# RPi_Extension_breakout.net
KiCad netlist of a schematic drawn in EAGLE
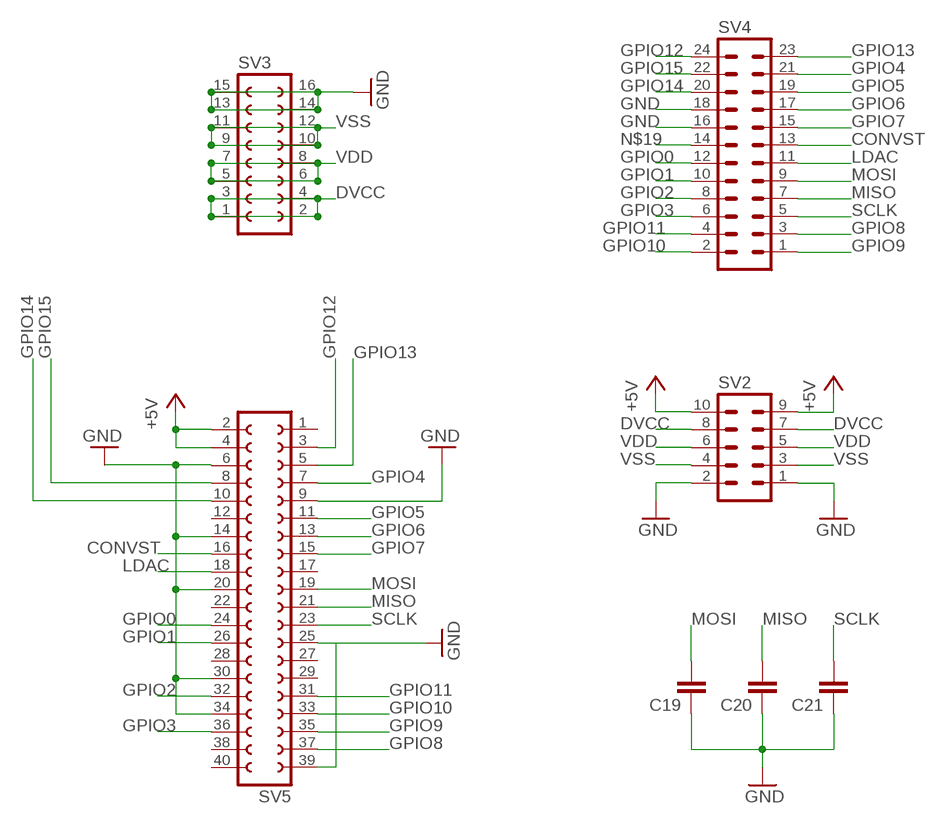
[diagram p0: schematic, sheet 1]

(export (version "E")
  (design (tool "Eeschema 10.0.6"))
  (components
    (comp (ref "C19")
      (value "C-EUC0603")
      (footprint "eagle-import:C0603")
      (libsource (lib "eagle-import") (part "C-EUC0603"))
    )
    (comp (ref "C20")
      (value "C-EUC0603")
      (footprint "eagle-import:C0603")
      (libsource (lib "eagle-import") (part "C-EUC0603"))
    )
    (comp (ref "C21")
      (value "C-EUC0603")
      (footprint "eagle-import:C0603")
      (libsource (lib "eagle-import") (part "C-EUC0603"))
    )
    (comp (ref "SV2")
      (value "MA05-2")
      (footprint "eagle-import:MA05-2")
      (libsource (lib "eagle-import") (part "MA05-2"))
    )
    (comp (ref "SV3")
      (value "FE08-2")
      (footprint "eagle-import:FE08-2")
      (libsource (lib "eagle-import") (part "FE08-2"))
    )
    (comp (ref "SV4")
      (value "MA12-2")
      (footprint "eagle-import:MA12-2")
      (libsource (lib "eagle-import") (part "MA12-2"))
    )
    (comp (ref "SV5")
      (value "FE20-2")
      (footprint "eagle-import:FE20-2")
      (libsource (lib "eagle-import") (part "FE20-2"))
    )
  )
  (nets
    (net (code "1") (name "+5V") (class "Default")
      (node (ref "SV2") (pin "10") (pinfunction "10_10") (pintype "passive"))
      (node (ref "SV2") (pin "9") (pinfunction "9_9") (pintype "passive"))
      (node (ref "SV5") (pin "2") (pinfunction "2_2") (pintype "passive"))
      (node (ref "SV5") (pin "4") (pinfunction "4_4") (pintype "passive"))
    )
    (net (code "2") (name "/CONVST") (class "Default")
      (node (ref "SV4") (pin "13") (pinfunction "13_13") (pintype "passive"))
      (node (ref "SV5") (pin "16") (pinfunction "16_16") (pintype "passive"))
    )
    (net (code "3") (name "/DVCC") (class "Default")
      (node (ref "SV2") (pin "7") (pinfunction "7_7") (pintype "passive"))
      (node (ref "SV2") (pin "8") (pinfunction "8_8") (pintype "passive"))
      (node (ref "SV3") (pin "1") (pinfunction "1_1") (pintype "passive"))
      (node (ref "SV3") (pin "2") (pinfunction "2_2") (pintype "passive"))
      (node (ref "SV3") (pin "3") (pinfunction "3_3") (pintype "passive"))
      (node (ref "SV3") (pin "4") (pinfunction "4_4") (pintype "passive"))
    )
    (net (code "4") (name "/GPIO0") (class "Default")
      (node (ref "SV4") (pin "12") (pinfunction "12_12") (pintype "passive"))
      (node (ref "SV5") (pin "24") (pinfunction "24_24") (pintype "passive"))
    )
    (net (code "5") (name "/GPIO1") (class "Default")
      (node (ref "SV4") (pin "10") (pinfunction "10_10") (pintype "passive"))
      (node (ref "SV5") (pin "26") (pinfunction "26_26") (pintype "passive"))
    )
    (net (code "6") (name "/GPIO2") (class "Default")
      (node (ref "SV4") (pin "8") (pinfunction "8_8") (pintype "passive"))
      (node (ref "SV5") (pin "32") (pinfunction "32_32") (pintype "passive"))
    )
    (net (code "7") (name "/GPIO3") (class "Default")
      (node (ref "SV4") (pin "6") (pinfunction "6_6") (pintype "passive"))
      (node (ref "SV5") (pin "36") (pinfunction "36_36") (pintype "passive"))
    )
    (net (code "8") (name "/GPIO4") (class "Default")
      (node (ref "SV4") (pin "21") (pinfunction "21_21") (pintype "passive"))
      (node (ref "SV5") (pin "7") (pinfunction "7_7") (pintype "passive"))
    )
    (net (code "9") (name "/GPIO5") (class "Default")
      (node (ref "SV4") (pin "19") (pinfunction "19_19") (pintype "passive"))
      (node (ref "SV5") (pin "11") (pinfunction "11_11") (pintype "passive"))
    )
    (net (code "10") (name "/GPIO6") (class "Default")
      (node (ref "SV4") (pin "17") (pinfunction "17_17") (pintype "passive"))
      (node (ref "SV5") (pin "13") (pinfunction "13_13") (pintype "passive"))
    )
    (net (code "11") (name "/GPIO7") (class "Default")
      (node (ref "SV4") (pin "15") (pinfunction "15_15") (pintype "passive"))
      (node (ref "SV5") (pin "15") (pinfunction "15_15") (pintype "passive"))
    )
    (net (code "12") (name "/GPIO8") (class "Default")
      (node (ref "SV4") (pin "3") (pinfunction "3_3") (pintype "passive"))
      (node (ref "SV5") (pin "37") (pinfunction "37_37") (pintype "passive"))
    )
    (net (code "13") (name "/GPIO9") (class "Default")
      (node (ref "SV4") (pin "1") (pinfunction "1_1") (pintype "passive"))
      (node (ref "SV5") (pin "35") (pinfunction "35_35") (pintype "passive"))
    )
    (net (code "14") (name "/GPIO10") (class "Default")
      (node (ref "SV4") (pin "2") (pinfunction "2_2") (pintype "passive"))
      (node (ref "SV5") (pin "33") (pinfunction "33_33") (pintype "passive"))
    )
    (net (code "15") (name "/GPIO11") (class "Default")
      (node (ref "SV4") (pin "4") (pinfunction "4_4") (pintype "passive"))
      (node (ref "SV5") (pin "31") (pinfunction "31_31") (pintype "passive"))
    )
    (net (code "16") (name "/GPIO12") (class "Default")
      (node (ref "SV4") (pin "24") (pinfunction "24_24") (pintype "passive"))
      (node (ref "SV5") (pin "3") (pinfunction "3_3") (pintype "passive"))
    )
    (net (code "17") (name "/GPIO13") (class "Default")
      (node (ref "SV4") (pin "23") (pinfunction "23_23") (pintype "passive"))
      (node (ref "SV5") (pin "5") (pinfunction "5_5") (pintype "passive"))
    )
    (net (code "18") (name "/GPIO14") (class "Default")
      (node (ref "SV4") (pin "20") (pinfunction "20_20") (pintype "passive"))
      (node (ref "SV5") (pin "10") (pinfunction "10_10") (pintype "passive"))
    )
    (net (code "19") (name "/GPIO15") (class "Default")
      (node (ref "SV4") (pin "22") (pinfunction "22_22") (pintype "passive"))
      (node (ref "SV5") (pin "8") (pinfunction "8_8") (pintype "passive"))
    )
    (net (code "20") (name "/LDAC") (class "Default")
      (node (ref "SV4") (pin "11") (pinfunction "11_11") (pintype "passive"))
      (node (ref "SV5") (pin "18") (pinfunction "18_18") (pintype "passive"))
    )
    (net (code "21") (name "/MISO") (class "Default")
      (node (ref "C20") (pin "2") (pinfunction "2_2") (pintype "passive"))
      (node (ref "SV4") (pin "7") (pinfunction "7_7") (pintype "passive"))
      (node (ref "SV5") (pin "21") (pinfunction "21_21") (pintype "passive"))
    )
    (net (code "22") (name "/MOSI") (class "Default")
      (node (ref "C19") (pin "2") (pinfunction "2_2") (pintype "passive"))
      (node (ref "SV4") (pin "9") (pinfunction "9_9") (pintype "passive"))
      (node (ref "SV5") (pin "19") (pinfunction "19_19") (pintype "passive"))
    )
    (net (code "23") (name "/N$19") (class "Default")
      (node (ref "SV4") (pin "14") (pinfunction "14_14") (pintype "passive"))
    )
    (net (code "24") (name "/SCLK") (class "Default")
      (node (ref "C21") (pin "2") (pinfunction "2_2") (pintype "passive"))
      (node (ref "SV4") (pin "5") (pinfunction "5_5") (pintype "passive"))
      (node (ref "SV5") (pin "23") (pinfunction "23_23") (pintype "passive"))
    )
    (net (code "25") (name "/VDD") (class "Default")
      (node (ref "SV2") (pin "5") (pinfunction "5_5") (pintype "passive"))
      (node (ref "SV2") (pin "6") (pinfunction "6_6") (pintype "passive"))
      (node (ref "SV3") (pin "5") (pinfunction "5_5") (pintype "passive"))
      (node (ref "SV3") (pin "6") (pinfunction "6_6") (pintype "passive"))
      (node (ref "SV3") (pin "7") (pinfunction "7_7") (pintype "passive"))
      (node (ref "SV3") (pin "8") (pinfunction "8_8") (pintype "passive"))
    )
    (net (code "26") (name "/VSS") (class "Default")
      (node (ref "SV2") (pin "3") (pinfunction "3_3") (pintype "passive"))
      (node (ref "SV2") (pin "4") (pinfunction "4_4") (pintype "passive"))
      (node (ref "SV3") (pin "10") (pinfunction "10_10") (pintype "passive"))
      (node (ref "SV3") (pin "11") (pinfunction "11_11") (pintype "passive"))
      (node (ref "SV3") (pin "12") (pinfunction "12_12") (pintype "passive"))
      (node (ref "SV3") (pin "9") (pinfunction "9_9") (pintype "passive"))
    )
    (net (code "27") (name "GND") (class "Default")
      (node (ref "C19") (pin "1") (pinfunction "1_1") (pintype "passive"))
      (node (ref "C20") (pin "1") (pinfunction "1_1") (pintype "passive"))
      (node (ref "C21") (pin "1") (pinfunction "1_1") (pintype "passive"))
      (node (ref "SV2") (pin "1") (pinfunction "1_1") (pintype "passive"))
      (node (ref "SV2") (pin "2") (pinfunction "2_2") (pintype "passive"))
      (node (ref "SV3") (pin "13") (pinfunction "13_13") (pintype "passive"))
      (node (ref "SV3") (pin "14") (pinfunction "14_14") (pintype "passive"))
      (node (ref "SV3") (pin "15") (pinfunction "15_15") (pintype "passive"))
      (node (ref "SV3") (pin "16") (pinfunction "16_16") (pintype "passive"))
      (node (ref "SV4") (pin "16") (pinfunction "16_16") (pintype "passive"))
      (node (ref "SV4") (pin "18") (pinfunction "18_18") (pintype "passive"))
      (node (ref "SV5") (pin "14") (pinfunction "14_14") (pintype "passive"))
      (node (ref "SV5") (pin "20") (pinfunction "20_20") (pintype "passive"))
      (node (ref "SV5") (pin "25") (pinfunction "25_25") (pintype "passive"))
      (node (ref "SV5") (pin "30") (pinfunction "30_30") (pintype "passive"))
      (node (ref "SV5") (pin "34") (pinfunction "34_34") (pintype "passive"))
      (node (ref "SV5") (pin "39") (pinfunction "39_39") (pintype "passive"))
      (node (ref "SV5") (pin "6") (pinfunction "6_6") (pintype "passive"))
      (node (ref "SV5") (pin "9") (pinfunction "9_9") (pintype "passive"))
    )
    (net (code "28") (name "unconnected-(SV5-Pad1)") (class "Default")
      (node (ref "SV5") (pin "1") (pinfunction "1_1") (pintype "passive"))
    )
    (net (code "29") (name "unconnected-(SV5-Pad12)") (class "Default")
      (node (ref "SV5") (pin "12") (pinfunction "12_12") (pintype "passive"))
    )
    (net (code "30") (name "unconnected-(SV5-Pad17)") (class "Default")
      (node (ref "SV5") (pin "17") (pinfunction "17_17") (pintype "passive"))
    )
    (net (code "31") (name "unconnected-(SV5-Pad22)") (class "Default")
      (node (ref "SV5") (pin "22") (pinfunction "22_22") (pintype "passive"))
    )
    (net (code "32") (name "unconnected-(SV5-Pad27)") (class "Default")
      (node (ref "SV5") (pin "27") (pinfunction "27_27") (pintype "passive"))
    )
    (net (code "33") (name "unconnected-(SV5-Pad28)") (class "Default")
      (node (ref "SV5") (pin "28") (pinfunction "28_28") (pintype "passive"))
    )
    (net (code "34") (name "unconnected-(SV5-Pad29)") (class "Default")
      (node (ref "SV5") (pin "29") (pinfunction "29_29") (pintype "passive"))
    )
    (net (code "35") (name "unconnected-(SV5-Pad38)") (class "Default")
      (node (ref "SV5") (pin "38") (pinfunction "38_38") (pintype "passive"))
    )
    (net (code "36") (name "unconnected-(SV5-Pad40)") (class "Default")
      (node (ref "SV5") (pin "40") (pinfunction "40_40") (pintype "passive"))
    )
  )
)
